# GSM_GPS.net
KiCad netlist of a schematic drawn in Altium Designer
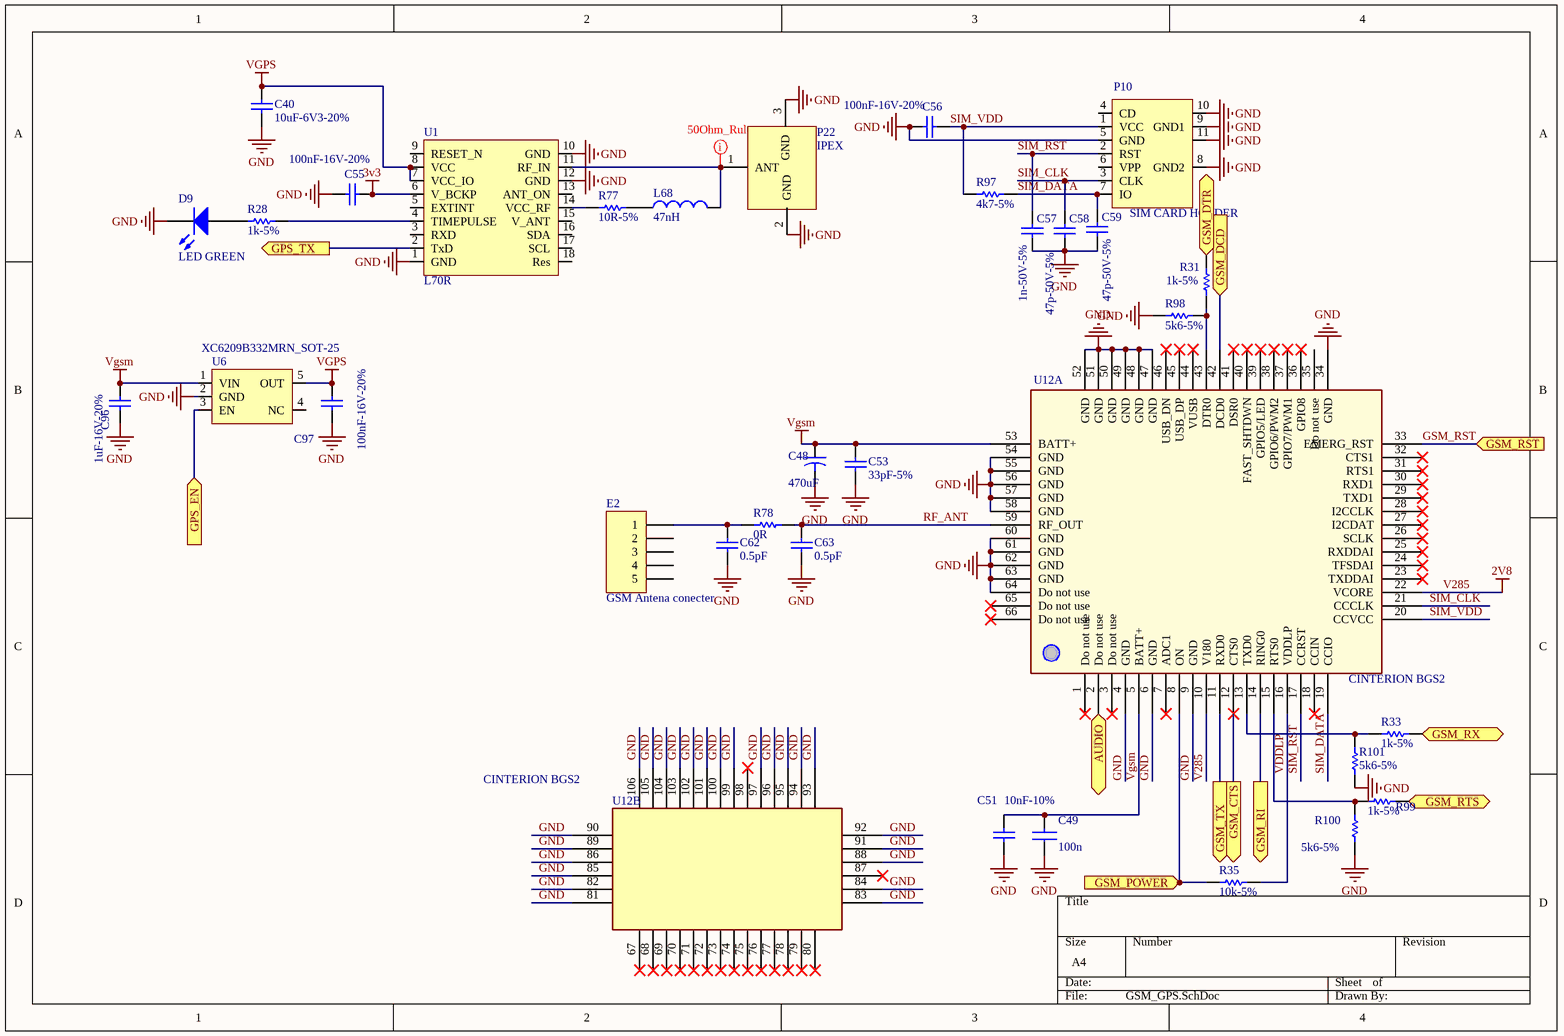
[diagram p0: GSM_GPS.SchDoc]

(export (version "E")
  (design (tool "Eeschema 10.0.6"))
  (components
    (comp (ref "C40")
      (value "10uF-6V3-20%")
      (footprint "C0603")
      (description "CAP CER 10UF 6.3V 20% X5R 0603")
      (fields
        (field (name "MANUFACTURER") "Murata Electronics North America")
        (field (name "DIGI-KEY PART NUMBER") "490-3896-1-ND")
        (field (name "PUBLISHER") "Altium Limited")
      )
      (libsource (lib "Miscellaneous Devices") (part "Cap"))
    )
    (comp (ref "C48")
      (value "470uF")
      (footprint "C2917_smd")
      (description "CAP TANT 470UF 6.3V 10% 2917")
      (fields
        (field (name "DIGI-KEY PART NUMBER") "399-4701-2-ND")
        (field (name "MANUFACTURER") "Kemet")
        (field (name "PUBLISHER") "Altium Limited")
      )
      (libsource (lib "Miscellaneous Devices") (part "Cap2"))
    )
    (comp (ref "C49")
      (value "100n")
      (footprint "0402_TYPE1")
      (description "CAP CER 0.1UF 16V 10% X7R 0805")
      (fields (field (name "DIGI-KEY PART NUMBER") "311-1142-2-ND") (field (name "MANUFACTURER") "Yageo"))
      (libsource (lib "*") (part "CAP NP"))
    )
    (comp (ref "C51")
      (value "10nF-10%")
      (footprint "0402_TYPE1")
      (description "Non-Polarized Capacitor")
      (fields (field (name "DIGI-KEY PART NUMBER") "311-1136-1-ND") (field (name "MANUFACTURER") "Yageo"))
      (libsource (lib "Capacitor") (part "10nF-50V-C0805"))
    )
    (comp (ref "C53")
      (value "33pF-5%")
      (footprint "0402_TYPE1")
      (description "Non-Polarized Capacitor")
      (fields (field (name "DIGI-KEY PART NUMBER") "311-1105-1-ND") (field (name "MANUFACTURER") "Yageo"))
      (libsource (lib "Capacitor") (part "33pF-50V-C0805"))
    )
    (comp (ref "C55")
      (value "100nF-16V-20%")
      (footprint "0402_TYPE1")
      (description "CAP CER 0.1UF 16V Y5V 0402")
      (fields
        (field (name "MANUFACTURER") "Yageo")
        (field (name "DIGI-KEY PART NUMBER") "311-1047-1-ND")
        (field (name "PUBLISHER") "Altium Limited")
      )
      (libsource (lib "Miscellaneous Devices") (part "Cap"))
    )
    (comp (ref "C56")
      (value "100nF-16V-20%")
      (footprint "0402_TYPE1")
      (description "CAP CER 0.1UF 16V Y5V 0402")
      (fields
        (field (name "MANUFACTURER") "Yageo")
        (field (name "DIGI-KEY PART NUMBER") "311-1047-1-ND")
        (field (name "PUBLISHER") "Altium Limited")
      )
      (libsource (lib "Miscellaneous Devices") (part "Cap"))
    )
    (comp (ref "C57")
      (value "1n-50V-5%")
      (footprint "0402_TYPE1")
      (description "CAP CER 47PF 50V 5% NPO 0402")
      (fields
        (field (name "MANUFACTURER") "Yageo")
        (field (name "DIGI-KEY PART NUMBER") "311-1021-1-ND")
        (field (name "PUBLISHER") "Altium Limited")
      )
      (libsource (lib "Miscellaneous Devices") (part "Cap"))
    )
    (comp (ref "C58")
      (value "47p-50V-5%")
      (footprint "0402_TYPE1")
      (description "CAP CER 47PF 50V 5% NPO 0402")
      (fields
        (field (name "MANUFACTURER") "Yageo")
        (field (name "DIGI-KEY PART NUMBER") "311-1021-1-ND")
        (field (name "PUBLISHER") "Altium Limited")
      )
      (libsource (lib "Miscellaneous Devices") (part "Cap"))
    )
    (comp (ref "C59")
      (value "47p-50V-5%")
      (footprint "0402_TYPE1")
      (description "CAP CER 47PF 50V 5% NPO 0402")
      (fields
        (field (name "MANUFACTURER") "Yageo")
        (field (name "DIGI-KEY PART NUMBER") "311-1021-1-ND")
        (field (name "PUBLISHER") "Altium Limited")
      )
      (libsource (lib "Miscellaneous Devices") (part "Cap"))
    )
    (comp (ref "C62")
      (value "0.5pF")
      (footprint "0402_TYPE1")
      (description "Non-Polarized Capacitor")
      (fields (field (name "DIGI-KEY PART NUMBER") "311-1094-1-ND") (field (name "MANUFACTURER") "Yageo"))
      (libsource (lib "Capacitor") (part "0.5pF-50V-C0805"))
    )
    (comp (ref "C63")
      (value "0.5pF")
      (footprint "0402_TYPE1")
      (description "Non-Polarized Capacitor")
      (fields (field (name "DIGI-KEY PART NUMBER") "311-1094-1-ND") (field (name "MANUFACTURER") "Yageo"))
      (libsource (lib "Capacitor") (part "0.5pF-50V-C0805"))
    )
    (comp (ref "C96")
      (value "1uF-16V-20%")
      (footprint "C0603")
      (description "CAP CER 1UF 16V Y5V 0603")
      (fields
        (field (name "MANUFACTURER") "Yageo")
        (field (name "DIGI-KEY PART NUMBER") "311-1372-1-ND")
        (field (name "PUBLISHER") "Altium Limited")
      )
      (libsource (lib "Miscellaneous Devices") (part "Cap"))
    )
    (comp (ref "C97")
      (value "100nF-16V-20%")
      (footprint "0402_TYPE1")
      (description "CAP CER 0.1UF 16V Y5V 0402")
      (fields
        (field (name "MANUFACTURER") "Yageo")
        (field (name "DIGI-KEY PART NUMBER") "311-1047-1-ND")
        (field (name "PUBLISHER") "Altium Limited")
      )
      (libsource (lib "Miscellaneous Devices") (part "Cap"))
    )
    (comp (ref "D9")
      (value "LED GREEN")
      (footprint "LED0603-G")
      (description "LED GREEN CLEAR THIN 0603 SMD")
      (fields
        (field (name "DIGI-KEY PART NUMBER") "160-1446-2-ND")
        (field (name "MANUFACTURER") "Lite-On Inc")
        (field (name "PUBLISHER") "Altium Limited")
      )
      (libsource (lib "Miscellaneous Devices") (part "LED2"))
    )
    (comp (ref "E2")
      (value "GSM Antena conecter")
      (footprint "A10343-GSM850/900/1800/1900/WCDMA")
      (description "Header, 5-Pin")
      (fields (field (name "PUBLISHER") "Altium Limited"))
      (libsource (lib "Miscellaneous Connectors") (part "Header 5"))
    )
    (comp (ref "L68")
      (value "47nH")
      (footprint "C0603")
      (description "Inductor")
      (fields (field (name "PUBLISHER") "Altium Limited"))
      (libsource (lib "Miscellaneous Devices") (part "Inductor"))
    )
    (comp (ref "P10")
      (value "SIM CARD HOLDER")
      (footprint "SIM MF01-412-063X")
      (description "SIM _CONNECTOR_410108105011-2LF")
      (fields (field (name "MANUFACTURER") "Tyrone"))
      (libsource (lib "Schlib1") (part "SIM CARD"))
    )
    (comp (ref "P22") (value "IPEX") (footprint "IPEX") (libsource (lib "Schlib1") (part "IPEX")))
    (comp (ref "R28")
      (value "1k-5%")
      (footprint "R0402_TYPE1")
      (description "RES 1.0K OHM 1/16W 5% 0402 SMD")
      (fields
        (field (name "DIGI-KEY PART NUMBER") "311-1.0KJRCT-ND")
        (field (name "MANUFACTURER") "Yageo")
        (field (name "PUBLISHER") "Altium Limited")
      )
      (libsource (lib "Miscellaneous Devices") (part "Res1"))
    )
    (comp (ref "R31")
      (value "1k-5%")
      (footprint "R0402_TYPE1")
      (description "RES 1.0K OHM 1/16W 5% 0402 SMD")
      (fields
        (field (name "DIGI-KEY PART NUMBER") "311-1.0KJRCT-ND")
        (field (name "MANUFACTURER") "Yageo")
        (field (name "PUBLISHER") "Altium Limited")
      )
      (libsource (lib "Miscellaneous Devices") (part "Res1"))
    )
    (comp (ref "R33")
      (value "1k-5%")
      (footprint "R0402_TYPE1")
      (description "RES 1.0K OHM 1/16W 5% 0402 SMD")
      (fields
        (field (name "DIGI-KEY PART NUMBER") "311-1.0KJRCT-ND")
        (field (name "MANUFACTURER") "Yageo")
        (field (name "PUBLISHER") "Altium Limited")
      )
      (libsource (lib "Miscellaneous Devices") (part "Res1"))
    )
    (comp (ref "R35")
      (value "10k-5%")
      (footprint "R0402_TYPE1")
      (description "RES 10K OHM 1/16W 5% 0402 SMD")
      (fields
        (field (name "DIGI-KEY PART NUMBER") "311-10KJRCT-ND")
        (field (name "MANUFACTURER") "Yageo")
        (field (name "PUBLISHER") "Altium Limited")
      )
      (libsource (lib "Miscellaneous Devices") (part "Res1"))
    )
    (comp (ref "R77")
      (value "10R-5%")
      (footprint "R0402_TYPE1")
      (description "RES 10 OHM 1/16W 5% 0402 SMD")
      (fields (field (name "DIGI-KEY PART NUMBER") "311-10JRTR-ND") (field (name "MANUFACTURER") "Yageo"))
      (libsource (lib "Resistor_0402") (part "10R-5%-R0402"))
    )
    (comp (ref "R78")
      (value "0R")
      (footprint "R0402_TYPE1")
      (libsource (lib "All_Resistor") (part "0R-0805"))
    )
    (comp (ref "R97")
      (value "4k7-5%")
      (footprint "R0402_TYPE1")
      (description "RES 4.7K OHM 1/16W 5% 0402 SMD")
      (fields
        (field (name "DIGI-KEY PART NUMBER") "311-4.7KJRCT-ND")
        (field (name "MANUFACTURER") "Yageo")
        (field (name "PUBLISHER") "Altium Limited")
      )
      (libsource (lib "Miscellaneous Devices") (part "Res1"))
    )
    (comp (ref "R98")
      (value "5k6-5%")
      (footprint "R0402_TYPE1")
      (description "RES 4.7K OHM 1/16W 5% 0402 SMD")
      (fields
        (field (name "DIGI-KEY PART NUMBER") "311-4.7KJRCT-ND")
        (field (name "MANUFACTURER") "Yageo")
        (field (name "PUBLISHER") "Altium Limited")
      )
      (libsource (lib "Miscellaneous Devices") (part "Res1"))
    )
    (comp (ref "R99")
      (value "1k-5%")
      (footprint "R0402_TYPE1")
      (description "RES 1.0K OHM 1/16W 5% 0402 SMD")
      (fields
        (field (name "DIGI-KEY PART NUMBER") "311-1.0KJRCT-ND")
        (field (name "MANUFACTURER") "Yageo")
        (field (name "PUBLISHER") "Altium Limited")
      )
      (libsource (lib "Miscellaneous Devices") (part "Res1"))
    )
    (comp (ref "R100")
      (value "5k6-5%")
      (footprint "R0402_TYPE1")
      (description "RES 4.7K OHM 1/16W 5% 0402 SMD")
      (fields
        (field (name "DIGI-KEY PART NUMBER") "311-4.7KJRCT-ND")
        (field (name "MANUFACTURER") "Yageo")
        (field (name "PUBLISHER") "Altium Limited")
      )
      (libsource (lib "Miscellaneous Devices") (part "Res1"))
    )
    (comp (ref "R101")
      (value "5k6-5%")
      (footprint "R0402_TYPE1")
      (description "RES 4.7K OHM 1/16W 5% 0402 SMD")
      (fields
        (field (name "DIGI-KEY PART NUMBER") "311-4.7KJRCT-ND")
        (field (name "MANUFACTURER") "Yageo")
        (field (name "PUBLISHER") "Altium Limited")
      )
      (libsource (lib "Miscellaneous Devices") (part "Res1"))
    )
    (comp (ref "U1") (value "L70R") (footprint "MAX7") (libsource (lib "U-Blox") (part "MAX-7")))
    (comp (ref "U6")
      (value "XC6209B332MRN_SOT-25")
      (footprint "SOT23-5")
      (fields (field (name "MANUFACTURER") "Tyrone"))
      (libsource (lib "Schlib1") (part "XC6209B332MRN_SOT-25"))
    )
    (comp (ref "U12")
      (value "CINTERION BGS2")
      (footprint "CINTERION BGS2")
      (description "CINTERION EHS5")
      (libsource (lib "IC") (part "CINTERION EHS5"))
    )
  )
  (nets
    (net (code "1") (name "/AUDIO") (class "Default")
      (node (ref "U12") (pin "2") (pinfunction "Do_not_use_2") (pintype "passive"))
    )
    (net (code "2") (name "/GPS_EN") (class "Default")
      (node (ref "U6") (pin "3") (pinfunction "EN_3") (pintype "passive"))
    )
    (net (code "3") (name "/GPS_TX") (class "Default")
      (node (ref "U1") (pin "2") (pinfunction "TxD_2") (pintype "passive"))
    )
    (net (code "4") (name "/GSM_CTS") (class "Default")
      (node (ref "U12") (pin "12") (pinfunction "CTS0_12") (pintype "passive+no_connect"))
    )
    (net (code "5") (name "/GSM_DCD") (class "Default")
      (node (ref "U12") (pin "42") (pinfunction "DCD0_42") (pintype "passive"))
    )
    (net (code "6") (name "/GSM_DTR") (class "Default")
      (node (ref "R31") (pin "1") (pinfunction "1_1") (pintype "passive"))
    )
    (net (code "7") (name "/GSM_POWER") (class "Default")
      (node (ref "R35") (pin "1") (pinfunction "1_1") (pintype "passive"))
      (node (ref "U12") (pin "8") (pinfunction "ON_8") (pintype "passive"))
    )
    (net (code "8") (name "/GSM_RI") (class "Default")
      (node (ref "U12") (pin "14") (pinfunction "RING0_14") (pintype "passive"))
    )
    (net (code "9") (name "/GSM_RST") (class "Default")
      (node (ref "U12") (pin "33") (pinfunction "EMERG_RST_33") (pintype "passive"))
    )
    (net (code "10") (name "/GSM_RTS") (class "Default")
      (node (ref "R99") (pin "2") (pinfunction "2_2") (pintype "passive"))
    )
    (net (code "11") (name "/GSM_RX") (class "Default")
      (node (ref "R33") (pin "2") (pinfunction "2_2") (pintype "passive"))
    )
    (net (code "12") (name "/GSM_TX") (class "Default")
      (node (ref "U12") (pin "11") (pinfunction "RXD0_11") (pintype "passive"))
    )
    (net (code "13") (name "/RF_ANT") (class "Default")
      (node (ref "C63") (pin "2") (pinfunction "2_2") (pintype "passive"))
      (node (ref "R78") (pin "1") (pinfunction "1_1") (pintype "passive"))
      (node (ref "U12") (pin "59") (pinfunction "RF_OUT_59") (pintype "passive"))
    )
    (net (code "14") (name "/SIM_CLK") (class "Default")
      (node (ref "C58") (pin "2") (pinfunction "2_2") (pintype "passive"))
      (node (ref "P10") (pin "3") (pinfunction "CLK_3") (pintype "passive"))
      (node (ref "U12") (pin "21") (pinfunction "CCCLK_21") (pintype "passive"))
    )
    (net (code "15") (name "/SIM_DATA") (class "Default")
      (node (ref "C59") (pin "2") (pinfunction "2_2") (pintype "passive"))
      (node (ref "P10") (pin "7") (pinfunction "IO_7") (pintype "passive"))
      (node (ref "R97") (pin "1") (pinfunction "1_1") (pintype "passive"))
      (node (ref "U12") (pin "19") (pinfunction "CCIO_19") (pintype "passive"))
    )
    (net (code "16") (name "/SIM_RST") (class "Default")
      (node (ref "C57") (pin "2") (pinfunction "2_2") (pintype "passive"))
      (node (ref "P10") (pin "2") (pinfunction "RST_2") (pintype "passive"))
      (node (ref "U12") (pin "17") (pinfunction "CCRST_17") (pintype "passive"))
    )
    (net (code "17") (name "/SIM_VDD") (class "Default")
      (node (ref "C56") (pin "1") (pinfunction "1_1") (pintype "passive"))
      (node (ref "P10") (pin "1") (pinfunction "VCC_1") (pintype "passive"))
      (node (ref "R97") (pin "2") (pinfunction "2_2") (pintype "passive"))
      (node (ref "U12") (pin "20") (pinfunction "CCVCC_20") (pintype "passive"))
    )
    (net (code "18") (name "/VDDLP") (class "Default")
      (node (ref "R35") (pin "2") (pinfunction "2_2") (pintype "passive"))
      (node (ref "U12") (pin "16") (pinfunction "VDDLP_16") (pintype "passive"))
    )
    (net (code "19") (name "2V8") (class "Default")
      (node (ref "U12") (pin "10") (pinfunction "V180_10") (pintype "passive"))
      (node (ref "U12") (pin "22") (pinfunction "VCORE_22") (pintype "passive"))
    )
    (net (code "20") (name "3v3") (class "Default")
      (node (ref "C55") (pin "1") (pinfunction "1_1") (pintype "passive"))
      (node (ref "U1") (pin "6") (pinfunction "V_BCKP_6") (pintype "passive"))
    )
    (net (code "21") (name "GND") (class "Default")
      (node (ref "C40") (pin "1") (pinfunction "1_1") (pintype "passive"))
      (node (ref "C48") (pin "2") (pinfunction "2_2") (pintype "passive"))
      (node (ref "C49") (pin "1") (pinfunction "1_1") (pintype "passive"))
      (node (ref "C51") (pin "1") (pinfunction "1_1") (pintype "passive"))
      (node (ref "C53") (pin "2") (pinfunction "2_2") (pintype "passive"))
      (node (ref "C55") (pin "2") (pinfunction "2_2") (pintype "passive"))
      (node (ref "C56") (pin "2") (pinfunction "2_2") (pintype "passive"))
      (node (ref "C57") (pin "1") (pinfunction "1_1") (pintype "passive"))
      (node (ref "C58") (pin "1") (pinfunction "1_1") (pintype "passive"))
      (node (ref "C59") (pin "1") (pinfunction "1_1") (pintype "passive"))
      (node (ref "C62") (pin "1") (pinfunction "1_1") (pintype "passive"))
      (node (ref "C63") (pin "1") (pinfunction "1_1") (pintype "passive"))
      (node (ref "C96") (pin "1") (pinfunction "1_1") (pintype "passive"))
      (node (ref "C97") (pin "1") (pinfunction "1_1") (pintype "passive"))
      (node (ref "D9") (pin "2") (pinfunction "K_2") (pintype "passive"))
      (node (ref "P10") (pin "10") (pinfunction "GND3_10") (pintype "passive"))
      (node (ref "P10") (pin "11") (pinfunction "GND4_11") (pintype "passive"))
      (node (ref "P10") (pin "5") (pinfunction "GND_5") (pintype "passive"))
      (node (ref "P10") (pin "8") (pinfunction "GND2_8") (pintype "passive"))
      (node (ref "P10") (pin "9") (pinfunction "GND1_9") (pintype "passive"))
      (node (ref "P22") (pin "2") (pinfunction "GND_2") (pintype "passive"))
      (node (ref "P22") (pin "3") (pinfunction "GND_3") (pintype "passive"))
      (node (ref "R100") (pin "2") (pinfunction "2_2") (pintype "passive"))
      (node (ref "R101") (pin "2") (pinfunction "2_2") (pintype "passive"))
      (node (ref "R98") (pin "2") (pinfunction "2_2") (pintype "passive"))
      (node (ref "U1") (pin "1") (pinfunction "GND_1") (pintype "passive"))
      (node (ref "U1") (pin "10") (pinfunction "GND_10") (pintype "passive"))
      (node (ref "U1") (pin "12") (pinfunction "GND_12") (pintype "passive"))
      (node (ref "U12") (pin "100") (pinfunction "GND_100") (pintype "passive"))
      (node (ref "U12") (pin "101") (pinfunction "GND_101") (pintype "passive"))
      (node (ref "U12") (pin "102") (pinfunction "GND_102") (pintype "passive"))
      (node (ref "U12") (pin "103") (pinfunction "GND_103") (pintype "passive"))
      (node (ref "U12") (pin "104") (pinfunction "GND_104") (pintype "passive"))
      (node (ref "U12") (pin "105") (pinfunction "GND_105") (pintype "passive"))
      (node (ref "U12") (pin "106") (pinfunction "GND_106") (pintype "passive"))
      (node (ref "U12") (pin "34") (pinfunction "GND_34") (pintype "passive"))
      (node (ref "U12") (pin "4") (pinfunction "GND_4") (pintype "passive"))
      (node (ref "U12") (pin "47") (pinfunction "GND_47") (pintype "passive"))
      (node (ref "U12") (pin "48") (pinfunction "GND_48") (pintype "passive"))
      (node (ref "U12") (pin "49") (pinfunction "GND_49") (pintype "passive"))
      (node (ref "U12") (pin "50") (pinfunction "GND_50") (pintype "passive"))
      (node (ref "U12") (pin "51") (pinfunction "GND_51") (pintype "passive"))
      (node (ref "U12") (pin "52") (pinfunction "GND_52") (pintype "passive"))
      (node (ref "U12") (pin "54") (pinfunction "GND_54") (pintype "passive"))
      (node (ref "U12") (pin "55") (pinfunction "GND_55") (pintype "passive"))
      (node (ref "U12") (pin "56") (pinfunction "GND_56") (pintype "passive"))
      (node (ref "U12") (pin "57") (pinfunction "GND_57") (pintype "passive"))
      (node (ref "U12") (pin "58") (pinfunction "GND_58") (pintype "passive"))
      (node (ref "U12") (pin "6") (pinfunction "GND_6") (pintype "passive"))
      (node (ref "U12") (pin "60") (pinfunction "GND_60") (pintype "passive"))
      (node (ref "U12") (pin "61") (pinfunction "GND_61") (pintype "passive"))
      (node (ref "U12") (pin "62") (pinfunction "GND_62") (pintype "passive"))
      (node (ref "U12") (pin "63") (pinfunction "GND_63") (pintype "passive"))
      (node (ref "U12") (pin "64") (pinfunction "Do_not_use_64") (pintype "passive"))
      (node (ref "U12") (pin "81") (pinfunction "GND_81") (pintype "passive"))
      (node (ref "U12") (pin "82") (pinfunction "GND_82") (pintype "passive"))
      (node (ref "U12") (pin "83") (pinfunction "GND_83") (pintype "passive"))
      (node (ref "U12") (pin "84") (pinfunction "GND_84") (pintype "passive"))
      (node (ref "U12") (pin "85") (pinfunction "GND_85") (pintype "passive"))
      (node (ref "U12") (pin "86") (pinfunction "GND_86") (pintype "passive"))
      (node (ref "U12") (pin "88") (pinfunction "GND_88") (pintype "passive"))
      (node (ref "U12") (pin "89") (pinfunction "GND_89") (pintype "passive"))
      (node (ref "U12") (pin "9") (pinfunction "GND_9") (pintype "passive"))
      (node (ref "U12") (pin "90") (pinfunction "GND_90") (pintype "passive"))
      (node (ref "U12") (pin "91") (pinfunction "GND_91") (pintype "passive"))
      (node (ref "U12") (pin "92") (pinfunction "GND_92") (pintype "passive"))
      (node (ref "U12") (pin "93") (pinfunction "GND_93") (pintype "passive"))
      (node (ref "U12") (pin "94") (pinfunction "GND_94") (pintype "passive"))
      (node (ref "U12") (pin "95") (pinfunction "GND_95") (pintype "passive"))
      (node (ref "U12") (pin "96") (pinfunction "GND_96") (pintype "passive"))
      (node (ref "U12") (pin "97") (pinfunction "GND_97") (pintype "passive"))
      (node (ref "U12") (pin "99") (pinfunction "GND_99") (pintype "passive"))
      (node (ref "U6") (pin "2") (pinfunction "GND_2") (pintype "passive"))
    )
    (net (code "22") (name "Net-(C62-Pad2)") (class "Default")
      (node (ref "C62") (pin "2") (pinfunction "2_2") (pintype "passive"))
      (node (ref "E2") (pin "1") (pinfunction "1_1") (pintype "passive"))
      (node (ref "R78") (pin "2") (pinfunction "2_2") (pintype "passive"))
    )
    (net (code "23") (name "Net-(D9-A)") (class "Default")
      (node (ref "D9") (pin "1") (pinfunction "A_1") (pintype "passive"))
      (node (ref "R28") (pin "2") (pinfunction "2_2") (pintype "passive"))
    )
    (net (code "24") (name "Net-(L68-Pad1)") (class "Default")
      (node (ref "L68") (pin "1") (pinfunction "1_1") (pintype "passive"))
      (node (ref "R77") (pin "1") (pinfunction "1_1") (pintype "passive"))
    )
    (net (code "25") (name "Net-(P22-ANT)") (class "Default")
      (node (ref "L68") (pin "2") (pinfunction "2_2") (pintype "passive"))
      (node (ref "P22") (pin "1") (pinfunction "ANT_1") (pintype "passive"))
      (node (ref "U1") (pin "11") (pinfunction "RF_IN_11") (pintype "passive"))
    )
    (net (code "26") (name "Net-(U1-TIMEPULSE)") (class "Default")
      (node (ref "R28") (pin "1") (pinfunction "1_1") (pintype "passive"))
      (node (ref "U1") (pin "4") (pinfunction "TIMEPULSE_4") (pintype "passive"))
    )
    (net (code "27") (name "Net-(U1-VCC_RF)") (class "Default")
      (node (ref "R77") (pin "2") (pinfunction "2_2") (pintype "passive"))
      (node (ref "U1") (pin "14") (pinfunction "VCC_RF_14") (pintype "passive"))
    )
    (net (code "28") (name "Net-(U12A-DTR0)") (class "Default")
      (node (ref "R31") (pin "2") (pinfunction "2_2") (pintype "passive"))
      (node (ref "R98") (pin "1") (pinfunction "1_1") (pintype "passive"))
      (node (ref "U12") (pin "43") (pinfunction "DTR0_43") (pintype "passive"))
    )
    (net (code "29") (name "Net-(U12A-RTS0)") (class "Default")
      (node (ref "R100") (pin "1") (pinfunction "1_1") (pintype "passive"))
      (node (ref "R99") (pin "1") (pinfunction "1_1") (pintype "passive"))
      (node (ref "U12") (pin "15") (pinfunction "RTS0_15") (pintype "passive"))
    )
    (net (code "30") (name "Net-(U12A-TXD0)") (class "Default")
      (node (ref "R101") (pin "1") (pinfunction "1_1") (pintype "passive"))
      (node (ref "R33") (pin "1") (pinfunction "1_1") (pintype "passive"))
      (node (ref "U12") (pin "13") (pinfunction "TXD0_13") (pintype "passive"))
    )
    (net (code "31") (name "VGPS") (class "Default")
      (node (ref "C40") (pin "2") (pinfunction "2_2") (pintype "passive"))
      (node (ref "C97") (pin "2") (pinfunction "2_2") (pintype "passive"))
      (node (ref "U1") (pin "7") (pinfunction "VCC_IO_7") (pintype "passive"))
      (node (ref "U1") (pin "8") (pinfunction "VCC_8") (pintype "passive"))
      (node (ref "U6") (pin "5") (pinfunction "OUT_5") (pintype "passive"))
    )
    (net (code "32") (name "Vgsm") (class "Default")
      (node (ref "C48") (pin "1") (pinfunction "1_1") (pintype "passive"))
      (node (ref "C49") (pin "2") (pinfunction "2_2") (pintype "passive"))
      (node (ref "C51") (pin "2") (pinfunction "2_2") (pintype "passive"))
      (node (ref "C53") (pin "1") (pinfunction "1_1") (pintype "passive"))
      (node (ref "C96") (pin "2") (pinfunction "2_2") (pintype "passive"))
      (node (ref "U12") (pin "5") (pinfunction "BATT+_5") (pintype "passive"))
      (node (ref "U12") (pin "53") (pinfunction "BATT+_53") (pintype "passive"))
      (node (ref "U6") (pin "1") (pinfunction "VIN_1") (pintype "passive"))
    )
    (net (code "33") (name "unconnected-(E2-Pad2)") (class "Default")
      (node (ref "E2") (pin "2") (pinfunction "2_2") (pintype "passive"))
    )
    (net (code "34") (name "unconnected-(E2-Pad3)") (class "Default")
      (node (ref "E2") (pin "3") (pinfunction "3_3") (pintype "passive"))
    )
    (net (code "35") (name "unconnected-(E2-Pad4)") (class "Default")
      (node (ref "E2") (pin "4") (pinfunction "4_4") (pintype "passive"))
    )
    (net (code "36") (name "unconnected-(E2-Pad5)") (class "Default")
      (node (ref "E2") (pin "5") (pinfunction "5_5") (pintype "passive"))
    )
    (net (code "37") (name "unconnected-(P10-CD-Pad4)") (class "Default")
      (node (ref "P10") (pin "4") (pinfunction "CD_4") (pintype "passive"))
    )
    (net (code "38") (name "unconnected-(P10-VPP-Pad6)") (class "Default")
      (node (ref "P10") (pin "6") (pinfunction "VPP_6") (pintype "passive"))
    )
    (net (code "39") (name "unconnected-(U1-ANT_ON-Pad13)") (class "Default")
      (node (ref "U1") (pin "13") (pinfunction "ANT_ON_13") (pintype "passive"))
    )
    (net (code "40") (name "unconnected-(U1-EXTINT-Pad5)") (class "Default")
      (node (ref "U1") (pin "5") (pinfunction "EXTINT_5") (pintype "passive"))
    )
    (net (code "41") (name "unconnected-(U1-RESET_N-Pad9)") (class "Default")
      (node (ref "U1") (pin "9") (pinfunction "RESET_N_9") (pintype "passive"))
    )
    (net (code "42") (name "unconnected-(U1-RXD-Pad3)") (class "Default")
      (node (ref "U1") (pin "3") (pinfunction "RXD_3") (pintype "passive"))
    )
    (net (code "43") (name "unconnected-(U1-Res-Pad18)") (class "Default")
      (node (ref "U1") (pin "18") (pinfunction "Res_18") (pintype "passive"))
    )
    (net (code "44") (name "unconnected-(U1-SCL-Pad17)") (class "Default")
      (node (ref "U1") (pin "17") (pinfunction "SCL_17") (pintype "passive"))
    )
    (net (code "45") (name "unconnected-(U1-SDA-Pad16)") (class "Default")
      (node (ref "U1") (pin "16") (pinfunction "SDA_16") (pintype "passive"))
    )
    (net (code "46") (name "unconnected-(U1-V_ANT-Pad15)") (class "Default")
      (node (ref "U1") (pin "15") (pinfunction "V_ANT_15") (pintype "passive"))
    )
    (net (code "47") (name "unconnected-(U6-NC-Pad4)") (class "Default")
      (node (ref "U6") (pin "4") (pinfunction "NC_4") (pintype "passive"))
    )
    (net (code "48") (name "unconnected-(U12A-ADC1-Pad7)") (class "Default")
      (node (ref "U12") (pin "7") (pinfunction "ADC1_7") (pintype "passive+no_connect"))
    )
    (net (code "49") (name "unconnected-(U12A-CCIN-Pad18)") (class "Default")
      (node (ref "U12") (pin "18") (pinfunction "CCIN_18") (pintype "passive+no_connect"))
    )
    (net (code "50") (name "unconnected-(U12A-CTS1-Pad32)") (class "Default")
      (node (ref "U12") (pin "32") (pinfunction "CTS1_32") (pintype "passive+no_connect"))
    )
    (net (code "51") (name "unconnected-(U12A-DSR0-Pad41)") (class "Default")
      (node (ref "U12") (pin "41") (pinfunction "DSR0_41") (pintype "passive+no_connect"))
    )
    (net (code "52") (name "unconnected-(U12A-Do_not_use-Pad1)") (class "Default")
      (node (ref "U12") (pin "1") (pinfunction "Do_not_use_1") (pintype "passive+no_connect"))
    )
    (net (code "53") (name "unconnected-(U12A-Do_not_use-Pad3)") (class "Default")
      (node (ref "U12") (pin "3") (pinfunction "Do_not_use_3") (pintype "passive+no_connect"))
    )
    (net (code "54") (name "unconnected-(U12A-Do_not_use-Pad35)") (class "Default")
      (node (ref "U12") (pin "35") (pinfunction "Do_not_use_35") (pintype "passive"))
    )
    (net (code "55") (name "unconnected-(U12A-Do_not_use-Pad65)") (class "Default")
      (node (ref "U12") (pin "65") (pinfunction "Do_not_use_65") (pintype "passive+no_connect"))
    )
    (net (code "56") (name "unconnected-(U12A-Do_not_use-Pad66)") (class "Default")
      (node (ref "U12") (pin "66") (pinfunction "Do_not_use_66") (pintype "passive+no_connect"))
    )
    (net (code "57") (name "unconnected-(U12A-FAST_SHTDWN-Pad40)") (class "Default")
      (node (ref "U12") (pin "40") (pinfunction "FAST_SHTDWN_40") (pintype "passive+no_connect"))
    )
    (net (code "58") (name "unconnected-(U12A-GPIO5{slash}LED-Pad39)") (class "Default")
      (node (ref "U12") (pin "39") (pinfunction "GPIO5/LED_39") (pintype "passive+no_connect"))
    )
    (net (code "59") (name "unconnected-(U12A-GPIO6{slash}PWM2-Pad38)") (class "Default")
      (node (ref "U12") (pin "38") (pinfunction "GPIO6/PWM2_38") (pintype "passive+no_connect"))
    )
    (net (code "60") (name "unconnected-(U12A-GPIO7{slash}PWM1-Pad37)") (class "Default")
      (node (ref "U12") (pin "37") (pinfunction "GPIO7/PWM1_37") (pintype "passive+no_connect"))
    )
    (net (code "61") (name "unconnected-(U12A-GPIO8-Pad36)") (class "Default")
      (node (ref "U12") (pin "36") (pinfunction "GPIO8_36") (pintype "passive+no_connect"))
    )
    (net (code "62") (name "unconnected-(U12A-I2CCLK-Pad28)") (class "Default")
      (node (ref "U12") (pin "28") (pinfunction "I2CCLK_28") (pintype "passive+no_connect"))
    )
    (net (code "63") (name "unconnected-(U12A-I2CDAT-Pad27)") (class "Default")
      (node (ref "U12") (pin "27") (pinfunction "I2CDAT_27") (pintype "passive+no_connect"))
    )
    (net (code "64") (name "unconnected-(U12A-RTS1-Pad31)") (class "Default")
      (node (ref "U12") (pin "31") (pinfunction "RTS1_31") (pintype "passive+no_connect"))
    )
    (net (code "65") (name "unconnected-(U12A-RXD1-Pad30)") (class "Default")
      (node (ref "U12") (pin "30") (pinfunction "RXD1_30") (pintype "passive+no_connect"))
    )
    (net (code "66") (name "unconnected-(U12A-RXDDAI-Pad25)") (class "Default")
      (node (ref "U12") (pin "25") (pinfunction "RXDDAI_25") (pintype "passive+no_connect"))
    )
    (net (code "67") (name "unconnected-(U12A-SCLK-Pad26)") (class "Default")
      (node (ref "U12") (pin "26") (pinfunction "SCLK_26") (pintype "passive+no_connect"))
    )
    (net (code "68") (name "unconnected-(U12A-TFSDAI-Pad24)") (class "Default")
      (node (ref "U12") (pin "24") (pinfunction "TFSDAI_24") (pintype "passive+no_connect"))
    )
    (net (code "69") (name "unconnected-(U12A-TXD1-Pad29)") (class "Default")
      (node (ref "U12") (pin "29") (pinfunction "TXD1_29") (pintype "passive+no_connect"))
    )
    (net (code "70") (name "unconnected-(U12A-TXDDAI-Pad23)") (class "Default")
      (node (ref "U12") (pin "23") (pinfunction "TXDDAI_23") (pintype "passive+no_connect"))
    )
    (net (code "71") (name "unconnected-(U12A-USB_DN-Pad46)") (class "Default")
      (node (ref "U12") (pin "46") (pinfunction "USB_DN_46") (pintype "passive+no_connect"))
    )
    (net (code "72") (name "unconnected-(U12A-USB_DP-Pad45)") (class "Default")
      (node (ref "U12") (pin "45") (pinfunction "USB_DP_45") (pintype "passive+no_connect"))
    )
    (net (code "73") (name "unconnected-(U12A-VUSB-Pad44)") (class "Default")
      (node (ref "U12") (pin "44") (pinfunction "VUSB_44") (pintype "passive+no_connect"))
    )
    (net (code "74") (name "unconnected-(U12B-GND-Pad67)") (class "Default")
      (node (ref "U12") (pin "67") (pinfunction "GND_67") (pintype "passive+no_connect"))
    )
    (net (code "75") (name "unconnected-(U12B-GND-Pad68)") (class "Default")
      (node (ref "U12") (pin "68") (pinfunction "GND_68") (pintype "passive+no_connect"))
    )
    (net (code "76") (name "unconnected-(U12B-GND-Pad69)") (class "Default")
      (node (ref "U12") (pin "69") (pinfunction "GND_69") (pintype "passive+no_connect"))
    )
    (net (code "77") (name "unconnected-(U12B-GND-Pad70)") (class "Default")
      (node (ref "U12") (pin "70") (pinfunction "GND_70") (pintype "passive+no_connect"))
    )
    (net (code "78") (name "unconnected-(U12B-GND-Pad71)") (class "Default")
      (node (ref "U12") (pin "71") (pinfunction "GND_71") (pintype "passive+no_connect"))
    )
    (net (code "79") (name "unconnected-(U12B-GND-Pad72)") (class "Default")
      (node (ref "U12") (pin "72") (pinfunction "GND_72") (pintype "passive+no_connect"))
    )
    (net (code "80") (name "unconnected-(U12B-GND-Pad73)") (class "Default")
      (node (ref "U12") (pin "73") (pinfunction "GND_73") (pintype "passive+no_connect"))
    )
    (net (code "81") (name "unconnected-(U12B-GND-Pad74)") (class "Default")
      (node (ref "U12") (pin "74") (pinfunction "GND_74") (pintype "passive+no_connect"))
    )
    (net (code "82") (name "unconnected-(U12B-GND-Pad75)") (class "Default")
      (node (ref "U12") (pin "75") (pinfunction "GND_75") (pintype "passive+no_connect"))
    )
    (net (code "83") (name "unconnected-(U12B-GND-Pad76)") (class "Default")
      (node (ref "U12") (pin "76") (pinfunction "GND_76") (pintype "passive+no_connect"))
    )
    (net (code "84") (name "unconnected-(U12B-GND-Pad77)") (class "Default")
      (node (ref "U12") (pin "77") (pinfunction "GND_77") (pintype "passive+no_connect"))
    )
    (net (code "85") (name "unconnected-(U12B-GND-Pad78)") (class "Default")
      (node (ref "U12") (pin "78") (pinfunction "GND_78") (pintype "passive+no_connect"))
    )
    (net (code "86") (name "unconnected-(U12B-GND-Pad79)") (class "Default")
      (node (ref "U12") (pin "79") (pinfunction "GND_79") (pintype "passive+no_connect"))
    )
    (net (code "87") (name "unconnected-(U12B-GND-Pad80)") (class "Default")
      (node (ref "U12") (pin "80") (pinfunction "GND_80") (pintype "passive+no_connect"))
    )
    (net (code "88") (name "unconnected-(U12B-GND-Pad87)") (class "Default")
      (node (ref "U12") (pin "87") (pinfunction "GND_87") (pintype "passive+no_connect"))
    )
    (net (code "89") (name "unconnected-(U12B-GND-Pad98)") (class "Default")
      (node (ref "U12") (pin "98") (pinfunction "GND_98") (pintype "passive+no_connect"))
    )
  )
)
